# OSO-MISC-22-002_Sensor_Watch_Motion_Expr.net
KiCad netlist of a schematic drawn in EAGLE
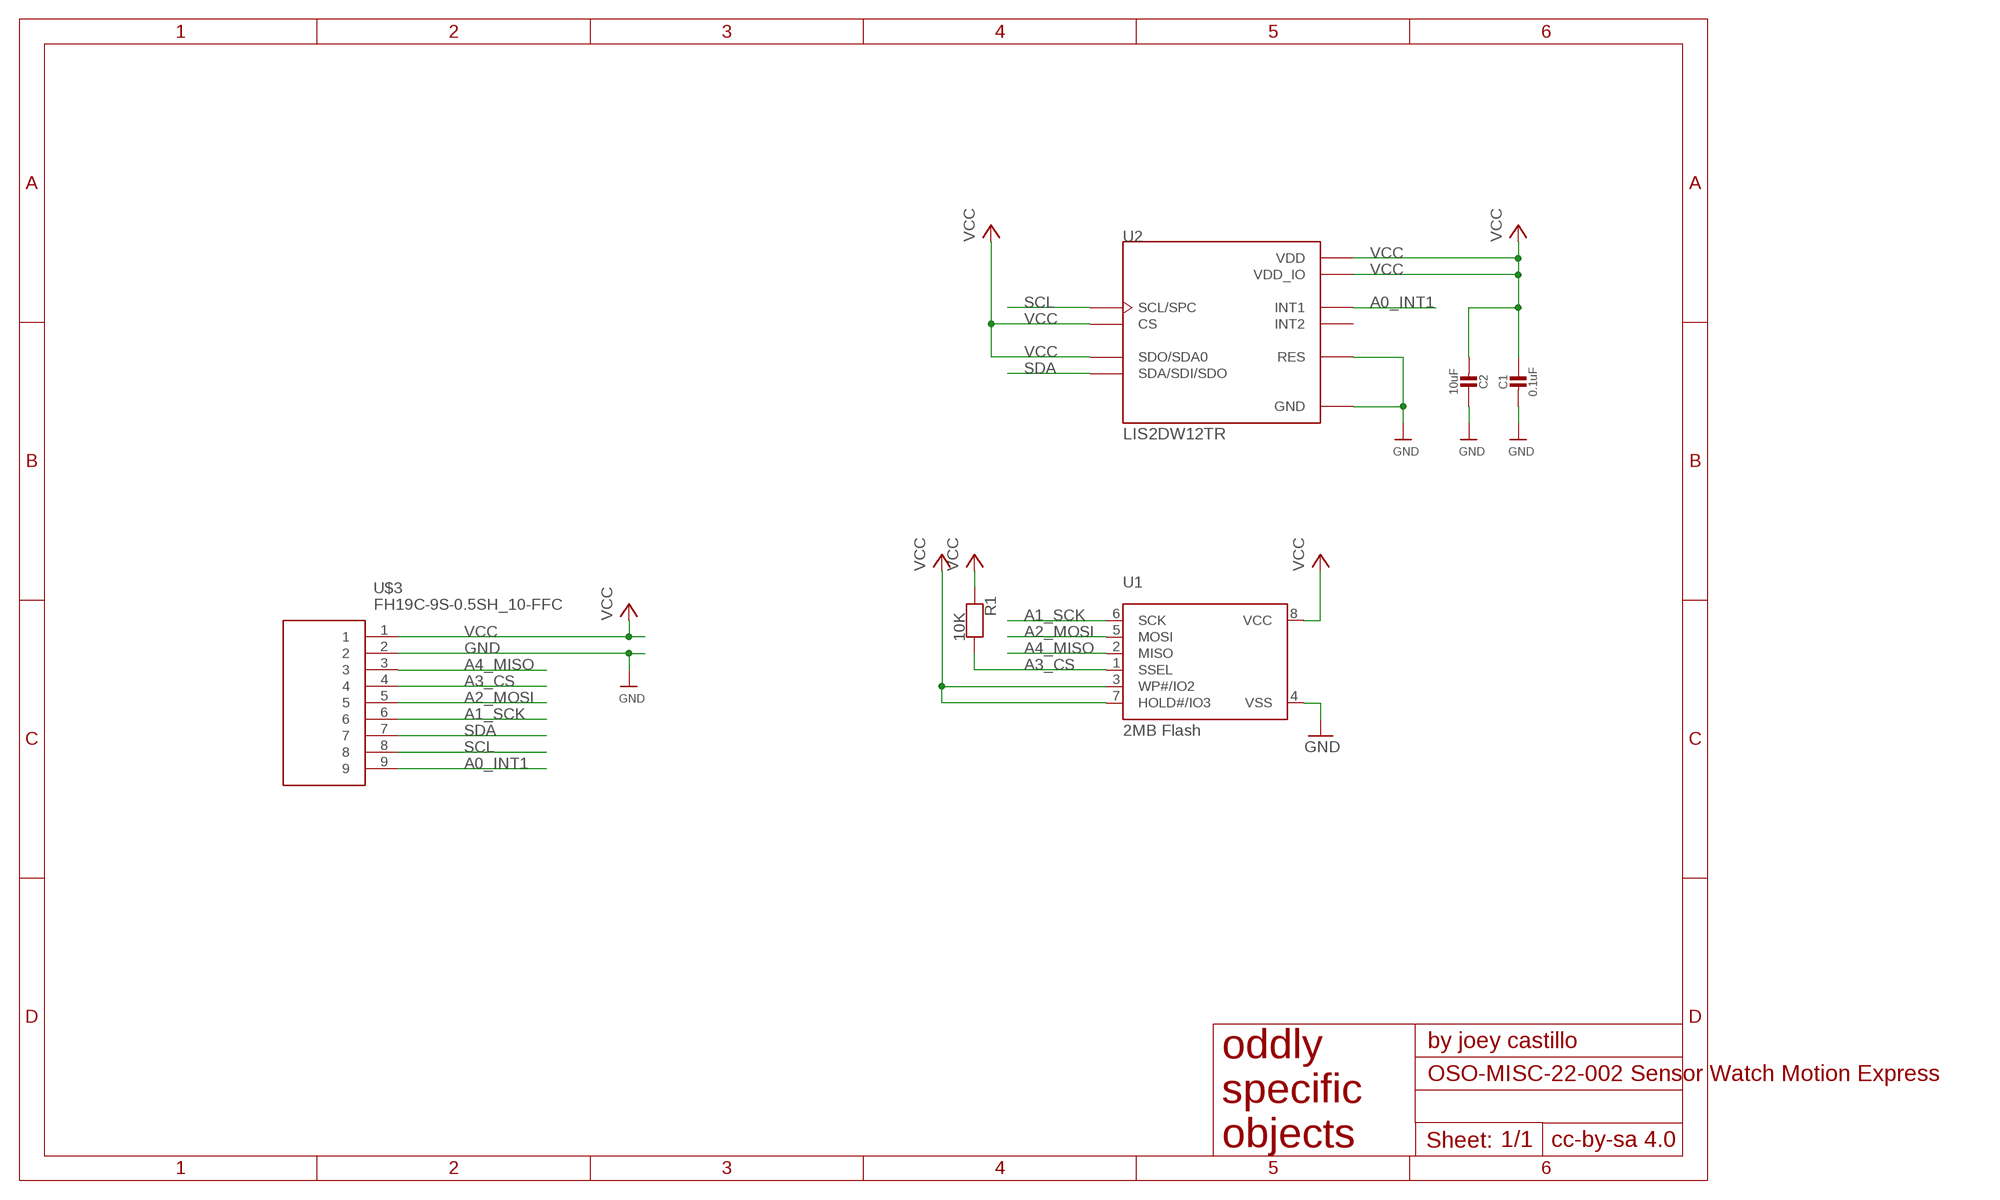
[diagram p0: schematic, sheet 1]

(export (version "E")
  (design (tool "Eeschema 10.0.6"))
  (components
    (comp (ref "C1")
      (value "0.1uF")
      (footprint "eagle-import:_0603MP")
      (libsource (lib "eagle-import") (part "CAP_CERAMIC_0603MP"))
    )
    (comp (ref "C2")
      (value "10uF")
      (footprint "eagle-import:_0603MP")
      (libsource (lib "eagle-import") (part "CAP_CERAMIC_0603MP"))
    )
    (comp (ref "R1")
      (value "10K")
      (footprint "eagle-import:_0603MP")
      (libsource (lib "eagle-import") (part "RESISTOR_0603MP"))
    )
    (comp (ref "U$3")
      (value "FH19C-9S-0.5SH_10-FFC")
      (footprint "eagle-import:FH19C9S05SH10-FFC")
      (libsource (lib "eagle-import") (part "FH19C-9S-0.5SH_10-FFC"))
    )
    (comp (ref "U1")
      (value "2MB Flash")
      (footprint "eagle-import:USON8")
      (libsource (lib "eagle-import") (part "SPIFLASH_8PINUX"))
    )
    (comp (ref "U2")
      (value "LIS2DW12TR")
      (footprint "eagle-import:LGA12R50P4X4_200X200X70")
      (fields (field (name "MF") "STMicroelectronics"))
      (libsource (lib "eagle-import") (part "LIS2DW12TR"))
    )
  )
  (nets
    (net (code "1") (name "/A0_INT1") (class "Default")
      (node (ref "U$3") (pin "9") (pinfunction "9_9") (pintype "bidirectional"))
      (node (ref "U2") (pin "12") (pinfunction "INT1_12") (pintype "output"))
    )
    (net (code "2") (name "/A1_SCK") (class "Default")
      (node (ref "U$3") (pin "6") (pinfunction "6_6") (pintype "bidirectional"))
      (node (ref "U1") (pin "6") (pinfunction "SCK_6") (pintype "bidirectional"))
    )
    (net (code "3") (name "/A2_MOSI") (class "Default")
      (node (ref "U$3") (pin "5") (pinfunction "5_5") (pintype "bidirectional"))
      (node (ref "U1") (pin "5") (pinfunction "MOSI_5") (pintype "bidirectional"))
    )
    (net (code "4") (name "/A3_CS") (class "Default")
      (node (ref "R1") (pin "2") (pinfunction "2_2") (pintype "passive"))
      (node (ref "U$3") (pin "4") (pinfunction "4_4") (pintype "bidirectional"))
      (node (ref "U1") (pin "1") (pinfunction "SSEL_1") (pintype "bidirectional"))
    )
    (net (code "5") (name "/A4_MISO") (class "Default")
      (node (ref "U$3") (pin "3") (pinfunction "3_3") (pintype "bidirectional"))
      (node (ref "U1") (pin "2") (pinfunction "MISO_2") (pintype "bidirectional"))
    )
    (net (code "6") (name "/SCL") (class "Default")
      (node (ref "U$3") (pin "8") (pinfunction "8_8") (pintype "bidirectional"))
      (node (ref "U2") (pin "1") (pinfunction "SCL/SPC_1") (pintype "input"))
    )
    (net (code "7") (name "/SDA") (class "Default")
      (node (ref "U$3") (pin "7") (pinfunction "7_7") (pintype "bidirectional"))
      (node (ref "U2") (pin "4") (pinfunction "SDA/SDI/SDO_4") (pintype "bidirectional"))
    )
    (net (code "8") (name "GND") (class "Default")
      (node (ref "C1") (pin "2") (pinfunction "2_2") (pintype "passive"))
      (node (ref "C2") (pin "1") (pinfunction "1_1") (pintype "passive"))
      (node (ref "U$3") (pin "2") (pinfunction "2_2") (pintype "bidirectional"))
      (node (ref "U1") (pin "4") (pinfunction "VSS_4") (pintype "bidirectional"))
      (node (ref "U2") (pin "6") (pinfunction "GND_6") (pintype "power_in"))
      (node (ref "U2") (pin "7") (pinfunction "RES_7") (pintype "passive"))
      (node (ref "U2") (pin "8") (pinfunction "GND_8") (pintype "power_in"))
    )
    (net (code "9") (name "VCC") (class "Default")
      (node (ref "C1") (pin "1") (pinfunction "1_1") (pintype "passive"))
      (node (ref "C2") (pin "2") (pinfunction "2_2") (pintype "passive"))
      (node (ref "R1") (pin "1") (pinfunction "1_1") (pintype "passive"))
      (node (ref "U$3") (pin "1") (pinfunction "1_1") (pintype "bidirectional"))
      (node (ref "U1") (pin "3") (pinfunction "WP#/IO2_3") (pintype "bidirectional"))
      (node (ref "U1") (pin "7") (pinfunction "HOLD#/IO3_7") (pintype "bidirectional"))
      (node (ref "U1") (pin "8") (pinfunction "VCC_8") (pintype "bidirectional"))
      (node (ref "U2") (pin "10") (pinfunction "VDD_IO_10") (pintype "power_in"))
      (node (ref "U2") (pin "2") (pinfunction "CS_2") (pintype "input"))
      (node (ref "U2") (pin "3") (pinfunction "SDO/SDA0_3") (pintype "bidirectional"))
      (node (ref "U2") (pin "9") (pinfunction "VDD_9") (pintype "power_in"))
    )
    (net (code "10") (name "unconnected-(U2-INT2-Pad11)") (class "Default")
      (node (ref "U2") (pin "11") (pinfunction "INT2_11") (pintype "output"))
    )
  )
)
